# Switch_Matrix_32_2_Supply.net
KiCad netlist of a schematic drawn in Altium Designer
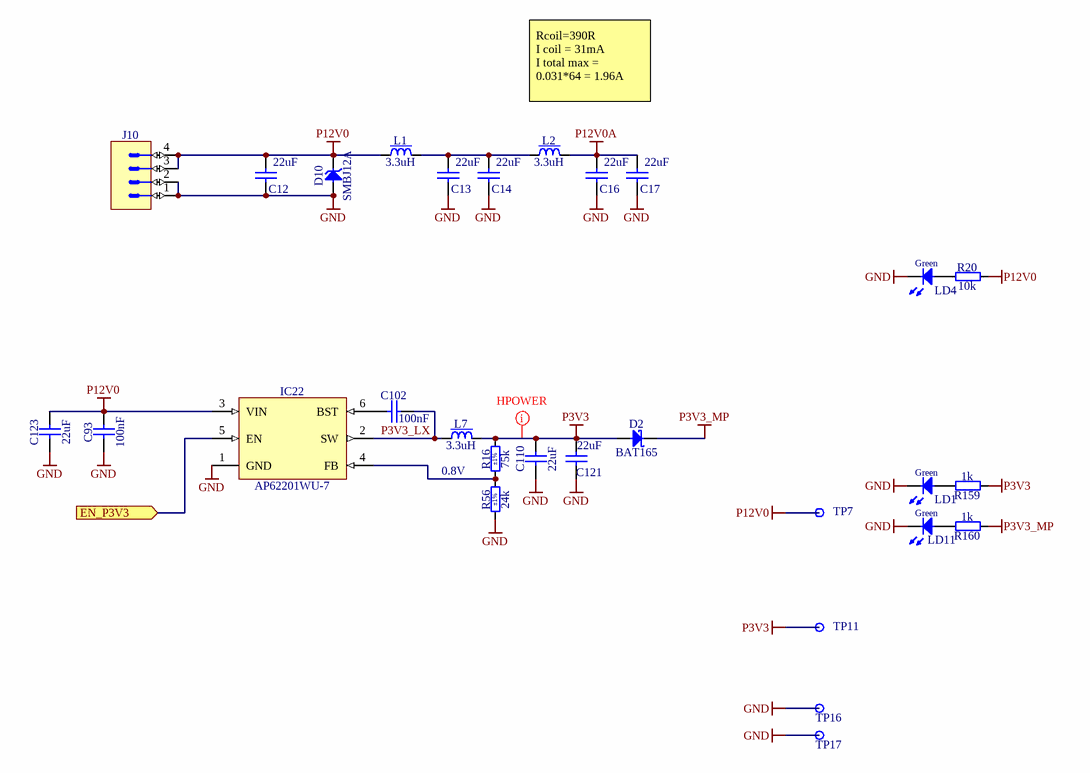
[diagram p0: Switch_Matrix_32_2_Supply.SchDoc]

(export (version "E")
  (design (tool "Eeschema 10.0.6"))
  (components
    (comp (ref "C12")
      (value "22uF")
      (footprint "CAPC2012X135N")
      (description "Non-polarised capacitor")
      (fields
        (field (name "PART NUMBER") "CC0805_22UF_16V_10%_X5R")
        (field (name "VOLTAGE") "16V")
        (field (name "AUTHOR") "CERN DEM JLC")
      )
      (libsource (lib "Capacitors") (part "Capacitor - non polarized"))
    )
    (comp (ref "C13")
      (value "22uF")
      (footprint "CAPC2012X135N")
      (description "Non-polarised capacitor")
      (fields
        (field (name "PART NUMBER") "CC0805_22UF_16V_10%_X5R")
        (field (name "VOLTAGE") "16V")
        (field (name "AUTHOR") "CERN DEM JLC")
      )
      (libsource (lib "Capacitors") (part "Capacitor - non polarized"))
    )
    (comp (ref "C14")
      (value "22uF")
      (footprint "CAPC2012X135N")
      (description "Non-polarised capacitor")
      (fields
        (field (name "PART NUMBER") "CC0805_22UF_16V_10%_X5R")
        (field (name "VOLTAGE") "16V")
        (field (name "AUTHOR") "CERN DEM JLC")
      )
      (libsource (lib "Capacitors") (part "Capacitor - non polarized"))
    )
    (comp (ref "C16")
      (value "22uF")
      (footprint "CAPC2012X135N")
      (description "Non-polarised capacitor")
      (fields
        (field (name "PART NUMBER") "CC0805_22UF_16V_10%_X5R")
        (field (name "VOLTAGE") "16V")
        (field (name "AUTHOR") "CERN DEM JLC")
      )
      (libsource (lib "Capacitors") (part "Capacitor - non polarized"))
    )
    (comp (ref "C17")
      (value "22uF")
      (footprint "CAPC2012X135N")
      (description "Non-polarised capacitor")
      (fields
        (field (name "PART NUMBER") "CC0805_22UF_16V_10%_X5R")
        (field (name "VOLTAGE") "16V")
        (field (name "AUTHOR") "CERN DEM JLC")
      )
      (libsource (lib "Capacitors") (part "Capacitor - non polarized"))
    )
    (comp (ref "C93")
      (value "100nF")
      (footprint "CAPC1608X87N")
      (description "Non-polarised capacitor")
      (fields
        (field (name "PART NUMBER") "CC0603_100NF_50V_10%_X7R")
        (field (name "VOLTAGE") "50V")
        (field (name "AUTHOR") "CERN DEM JLC")
      )
      (libsource (lib "Capacitors") (part "Capacitor - non polarized"))
    )
    (comp (ref "C102")
      (value "100nF")
      (footprint "CAPC1608X87N")
      (description "Non-polarised capacitor")
      (fields
        (field (name "PART NUMBER") "CC0603_100NF_50V_10%_X7R")
        (field (name "VOLTAGE") "50V")
        (field (name "AUTHOR") "CERN DEM JLC")
      )
      (libsource (lib "Capacitors") (part "Capacitor - non polarized"))
    )
    (comp (ref "C110")
      (value "22uF")
      (footprint "CAPC2012X135N")
      (description "Non-polarised capacitor")
      (fields
        (field (name "PART NUMBER") "CC0805_22UF_16V_10%_X5R")
        (field (name "VOLTAGE") "16V")
        (field (name "AUTHOR") "CERN DEM JLC")
      )
      (libsource (lib "Capacitors") (part "Capacitor - non polarized"))
    )
    (comp (ref "C121")
      (value "22uF")
      (footprint "CAPC2012X135N")
      (description "Non-polarised capacitor")
      (fields
        (field (name "PART NUMBER") "CC0805_22UF_16V_10%_X5R")
        (field (name "VOLTAGE") "16V")
        (field (name "AUTHOR") "CERN DEM JLC")
      )
      (libsource (lib "Capacitors") (part "Capacitor - non polarized"))
    )
    (comp (ref "C123")
      (value "22uF")
      (footprint "CAPC2012X135N")
      (description "Non-polarised capacitor")
      (fields
        (field (name "PART NUMBER") "CC0805_22UF_16V_10%_X5R")
        (field (name "VOLTAGE") "16V")
        (field (name "AUTHOR") "CERN DEM JLC")
      )
      (libsource (lib "Capacitors") (part "Capacitor - non polarized"))
    )
    (comp (ref "D2")
      (value "BAT165")
      (footprint "SOD2512X110N")
      (description "Schottky Diode")
      (fields
        (field (name "VOLTAGE") "40V")
        (field (name "POWER") "750mA")
        (field (name "AUTHOR") "CERN DEM JLC")
      )
      (libsource (lib "ICs And Semiconductors") (part "Diode Schottky"))
    )
    (comp (ref "D10")
      (value "SMBJ12A")
      (footprint "DIOM5336X265N")
      (description "Zener Diode")
      (fields
        (field (name "VOLTAGE") "12V")
        (field (name "POWER") "600W")
        (field (name "AUTHOR") "CERN DEM JLC")
      )
      (libsource (lib "ICs And Semiconductors") (part "Diode Zener"))
    )
    (comp (ref "IC22")
      (value "AP62201WU-7")
      (footprint "SOT95P280X100-6N")
      (description "4.2V TO 18V INPUT, 2A LOW IQ SYNCHRONOUS BUCK CONVERTER")
      (fields (field (name "MANUFACTURER") "DIODES INCORPORATED") (field (name "AUTHOR") "CERN DEM HF"))
      (libsource (lib "ICs And Semiconductors") (part "AP62201WU"))
    )
    (comp (ref "J10")
      (value "Mini-Fit Jr.™")
      (footprint "MOLEX_39-30-0040")
      (description "Connector 4 Male")
      (fields
        (field (name "PART NUMBER") "MOLEX_39-30-0040")
        (field (name "MANUFACTURER") "MOLEX")
        (field (name "AUTHOR") "CERN DEM JLC")
      )
      (libsource (lib "Connectors") (part "Connector 4 Male"))
    )
    (comp (ref "L1")
      (value "3.3uH")
      (footprint "IND_WURTH_WE-TPC_4828")
      (description "Inductor With Core")
      (fields
        (field (name "PART NUMBER") "IND_3.3UH_30%_WURTH_WE-TPC_744043003")
        (field (name "POWER") "2.15A")
        (field (name "AUTHOR") "CERN DEM JLC")
      )
      (libsource (lib "Inductors & Transformers") (part "Inductor With Magnetic core"))
    )
    (comp (ref "L2")
      (value "3.3uH")
      (footprint "IND_WURTH_WE-TPC_4828")
      (description "Inductor With Core")
      (fields
        (field (name "PART NUMBER") "IND_3.3UH_30%_WURTH_WE-TPC_744043003")
        (field (name "POWER") "2.15A")
        (field (name "AUTHOR") "CERN DEM JLC")
      )
      (libsource (lib "Inductors & Transformers") (part "Inductor With Magnetic core"))
    )
    (comp (ref "L7")
      (value "3.3uH")
      (footprint "IND_WURTH_WE-TPC_4828")
      (description "Inductor With Core")
      (fields
        (field (name "PART NUMBER") "IND_3.3UH_30%_WURTH_WE-TPC_744043003")
        (field (name "POWER") "2.15A")
        (field (name "AUTHOR") "CERN DEM JLC")
      )
      (libsource (lib "Inductors & Transformers") (part "Inductor With Magnetic core"))
    )
    (comp (ref "LD1")
      (value "Green")
      (footprint "LED_AVAGO_HSME-C110")
      (description "LED Green 1C 2A")
      (fields
        (field (name "PART NUMBER") "LED_AVAGO_HSME-C110")
        (field (name "MANUFACTURER") "AVAGO TECHNOLOGIES")
        (field (name "AUTHOR") "CERN DEM JMW")
      )
      (libsource (lib "ICs And Semiconductors") (part "LED Green 1C 2A"))
    )
    (comp (ref "LD4")
      (value "Green")
      (footprint "LED_KINGBRIGHT_KPH-1608CGCK")
      (description "LED Green 1C 2A")
      (fields
        (field (name "PART NUMBER") "LED_KINGBRIGHT_KPH-1608CGCK")
        (field (name "MANUFACTURER") "KINGBRIGHT")
        (field (name "AUTHOR") "CERN DEM JLC")
      )
      (libsource (lib "ICs And Semiconductors") (part "LED Green 1C 2A"))
    )
    (comp (ref "LD11")
      (value "Green")
      (footprint "LED_KINGBRIGHT_KPH-1608CGCK")
      (description "LED Green 1C 2A")
      (fields
        (field (name "PART NUMBER") "LED_KINGBRIGHT_KPH-1608CGCK")
        (field (name "MANUFACTURER") "KINGBRIGHT")
        (field (name "AUTHOR") "CERN DEM JLC")
      )
      (libsource (lib "ICs And Semiconductors") (part "LED Green 1C 2A"))
    )
    (comp (ref "R16")
      (value "75k")
      (footprint "RESC1608X55N")
      (description "Resistor - 1%")
      (fields
        (field (name "TOLERANCE") "±1%")
        (field (name "PART NUMBER") "R0603_75K_1%_0.1W_100PPM")
        (field (name "POWER") "0.1W")
        (field (name "AUTHOR") "CERN DEM JLC")
      )
      (libsource (lib "Resistors") (part "Resistor - 1%"))
    )
    (comp (ref "R20")
      (value "10k")
      (footprint "RESC1608X55N")
      (description "Resistor - 1%")
      (fields
        (field (name "PART NUMBER") "R0603_10K_1%_0.1W_100PPM")
        (field (name "POWER") "0.1W")
        (field (name "AUTHOR") "CERN DEM JLC")
      )
      (libsource (lib "Resistors") (part "Resistor - 1%"))
    )
    (comp (ref "R56")
      (value "24k")
      (footprint "RESC1608X55N")
      (description "Resistor - 1%")
      (fields
        (field (name "TOLERANCE") "±1%")
        (field (name "PART NUMBER") "R0603_24K_1%_0.1W_100PPM")
        (field (name "POWER") "0.1W")
        (field (name "AUTHOR") "CERN DEM JLC")
      )
      (libsource (lib "Resistors") (part "Resistor - 1%"))
    )
    (comp (ref "R159")
      (value "1k")
      (footprint "RESC1608X55N")
      (description "Resistor - 1%")
      (fields
        (field (name "PART NUMBER") "R0603_1K_1%_0.1W_100PPM")
        (field (name "POWER") "0.1W")
        (field (name "AUTHOR") "CERN DEM JLC")
      )
      (libsource (lib "Resistors") (part "Resistor - 1%"))
    )
    (comp (ref "R160")
      (value "1k")
      (footprint "RESC1608X55N")
      (description "Resistor - 1%")
      (fields
        (field (name "PART NUMBER") "R0603_1K_1%_0.1W_100PPM")
        (field (name "POWER") "0.1W")
        (field (name "AUTHOR") "CERN DEM JLC")
      )
      (libsource (lib "Resistors") (part "Resistor - 1%"))
    )
    (comp (ref "TP7")
      (value "Test Point")
      (footprint "TPS127")
      (fields (field (name "PART NUMBER") "SMD_PAD_1.27X1.27MM") (field (name "AUTHOR") "CERN DEM JLC"))
      (libsource (lib "Eletro-mechanical") (part "Test Point"))
    )
    (comp (ref "TP11")
      (value "Test Point")
      (footprint "TPS127")
      (fields (field (name "PART NUMBER") "SMD_PAD_1.27X1.27MM") (field (name "AUTHOR") "CERN DEM JLC"))
      (libsource (lib "Eletro-mechanical") (part "Test Point"))
    )
    (comp (ref "TP16")
      (value "Test Point")
      (footprint "TPS127")
      (fields (field (name "PART NUMBER") "SMD_PAD_1.27X1.27MM") (field (name "AUTHOR") "CERN DEM JLC"))
      (libsource (lib "Eletro-mechanical") (part "Test Point"))
    )
    (comp (ref "TP17")
      (value "Test Point")
      (footprint "TPS127")
      (fields (field (name "PART NUMBER") "SMD_PAD_1.27X1.27MM") (field (name "AUTHOR") "CERN DEM JLC"))
      (libsource (lib "Eletro-mechanical") (part "Test Point"))
    )
  )
  (nets
    (net (code "1") (name "/EN_P3V3") (class "Default")
      (node (ref "IC22") (pin "5") (pinfunction "EN_5") (pintype "input"))
    )
    (net (code "2") (name "/P3V3_LX") (class "Default")
      (node (ref "C102") (pin "2") (pinfunction "2_2") (pintype "passive"))
      (node (ref "IC22") (pin "2") (pinfunction "SW_2") (pintype "output"))
      (node (ref "L7") (pin "1") (pinfunction "1_1") (pintype "passive"))
    )
    (net (code "3") (name "GND") (class "Default")
      (node (ref "C110") (pin "1") (pinfunction "1_1") (pintype "passive"))
      (node (ref "C12") (pin "1") (pinfunction "1_1") (pintype "passive"))
      (node (ref "C121") (pin "1") (pinfunction "1_1") (pintype "passive"))
      (node (ref "C123") (pin "1") (pinfunction "1_1") (pintype "passive"))
      (node (ref "C13") (pin "1") (pinfunction "1_1") (pintype "passive"))
      (node (ref "C14") (pin "1") (pinfunction "1_1") (pintype "passive"))
      (node (ref "C16") (pin "1") (pinfunction "1_1") (pintype "passive"))
      (node (ref "C17") (pin "1") (pinfunction "1_1") (pintype "passive"))
      (node (ref "C93") (pin "1") (pinfunction "1_1") (pintype "passive"))
      (node (ref "D10") (pin "2") (pinfunction "A_2") (pintype "passive"))
      (node (ref "IC22") (pin "1") (pinfunction "GND_1") (pintype "power_in"))
      (node (ref "J10") (pin "1") (pinfunction "1_1") (pintype "bidirectional"))
      (node (ref "J10") (pin "2") (pinfunction "2_2") (pintype "bidirectional"))
      (node (ref "LD1") (pin "1") (pinfunction "C_1") (pintype "passive"))
      (node (ref "LD11") (pin "1") (pinfunction "C_1") (pintype "passive"))
      (node (ref "LD4") (pin "1") (pinfunction "C_1") (pintype "passive"))
      (node (ref "R56") (pin "1") (pinfunction "1_1") (pintype "passive"))
      (node (ref "TP16") (pin "1") (pinfunction "1_1") (pintype "bidirectional"))
      (node (ref "TP17") (pin "1") (pinfunction "1_1") (pintype "bidirectional"))
    )
    (net (code "4") (name "Net-(C13-Pad2)") (class "Default")
      (node (ref "C13") (pin "2") (pinfunction "2_2") (pintype "passive"))
      (node (ref "C14") (pin "2") (pinfunction "2_2") (pintype "passive"))
      (node (ref "L1") (pin "2") (pinfunction "2_2") (pintype "passive"))
      (node (ref "L2") (pin "1") (pinfunction "1_1") (pintype "passive"))
    )
    (net (code "5") (name "Net-(IC22-BST)") (class "Default")
      (node (ref "C102") (pin "1") (pinfunction "1_1") (pintype "passive"))
      (node (ref "IC22") (pin "6") (pinfunction "BST_6") (pintype "input"))
    )
    (net (code "6") (name "Net-(IC22-FB)") (class "Default")
      (node (ref "IC22") (pin "4") (pinfunction "FB_4") (pintype "input"))
      (node (ref "R16") (pin "1") (pinfunction "1_1") (pintype "passive"))
      (node (ref "R56") (pin "2") (pinfunction "2_2") (pintype "passive"))
    )
    (net (code "7") (name "Net-(LD1-A)") (class "Default")
      (node (ref "LD1") (pin "2") (pinfunction "A_2") (pintype "passive"))
      (node (ref "R159") (pin "2") (pinfunction "2_2") (pintype "passive"))
    )
    (net (code "8") (name "Net-(LD4-A)") (class "Default")
      (node (ref "LD4") (pin "2") (pinfunction "A_2") (pintype "passive"))
      (node (ref "R20") (pin "1") (pinfunction "1_1") (pintype "passive"))
    )
    (net (code "9") (name "Net-(LD11-A)") (class "Default")
      (node (ref "LD11") (pin "2") (pinfunction "A_2") (pintype "passive"))
      (node (ref "R160") (pin "2") (pinfunction "2_2") (pintype "passive"))
    )
    (net (code "10") (name "P3V3") (class "Default")
      (node (ref "C110") (pin "2") (pinfunction "2_2") (pintype "passive"))
      (node (ref "C121") (pin "2") (pinfunction "2_2") (pintype "passive"))
      (node (ref "D2") (pin "2") (pinfunction "A_2") (pintype "passive"))
      (node (ref "L7") (pin "2") (pinfunction "2_2") (pintype "passive"))
      (node (ref "R159") (pin "1") (pinfunction "1_1") (pintype "passive"))
      (node (ref "R16") (pin "2") (pinfunction "2_2") (pintype "passive"))
      (node (ref "TP11") (pin "1") (pinfunction "1_1") (pintype "bidirectional"))
    )
    (net (code "11") (name "P3V3_MP") (class "Default")
      (node (ref "D2") (pin "1") (pinfunction "C_1") (pintype "passive"))
      (node (ref "R160") (pin "1") (pinfunction "1_1") (pintype "passive"))
    )
    (net (code "12") (name "P12V0") (class "Default")
      (node (ref "C12") (pin "2") (pinfunction "2_2") (pintype "passive"))
      (node (ref "C123") (pin "2") (pinfunction "2_2") (pintype "passive"))
      (node (ref "C93") (pin "2") (pinfunction "2_2") (pintype "passive"))
      (node (ref "D10") (pin "1") (pinfunction "C_1") (pintype "passive"))
      (node (ref "IC22") (pin "3") (pinfunction "VIN_3") (pintype "input"))
      (node (ref "J10") (pin "3") (pinfunction "3_3") (pintype "bidirectional"))
      (node (ref "J10") (pin "4") (pinfunction "4_4") (pintype "bidirectional"))
      (node (ref "L1") (pin "1") (pinfunction "1_1") (pintype "passive"))
      (node (ref "R20") (pin "2") (pinfunction "2_2") (pintype "passive"))
      (node (ref "TP7") (pin "1") (pinfunction "1_1") (pintype "bidirectional"))
    )
    (net (code "13") (name "P12V0A") (class "Default")
      (node (ref "C16") (pin "2") (pinfunction "2_2") (pintype "passive"))
      (node (ref "C17") (pin "2") (pinfunction "2_2") (pintype "passive"))
      (node (ref "L2") (pin "2") (pinfunction "2_2") (pintype "passive"))
    )
  )
)
